# b294_rev0.net
KiCad netlist of a schematic drawn in EAGLE
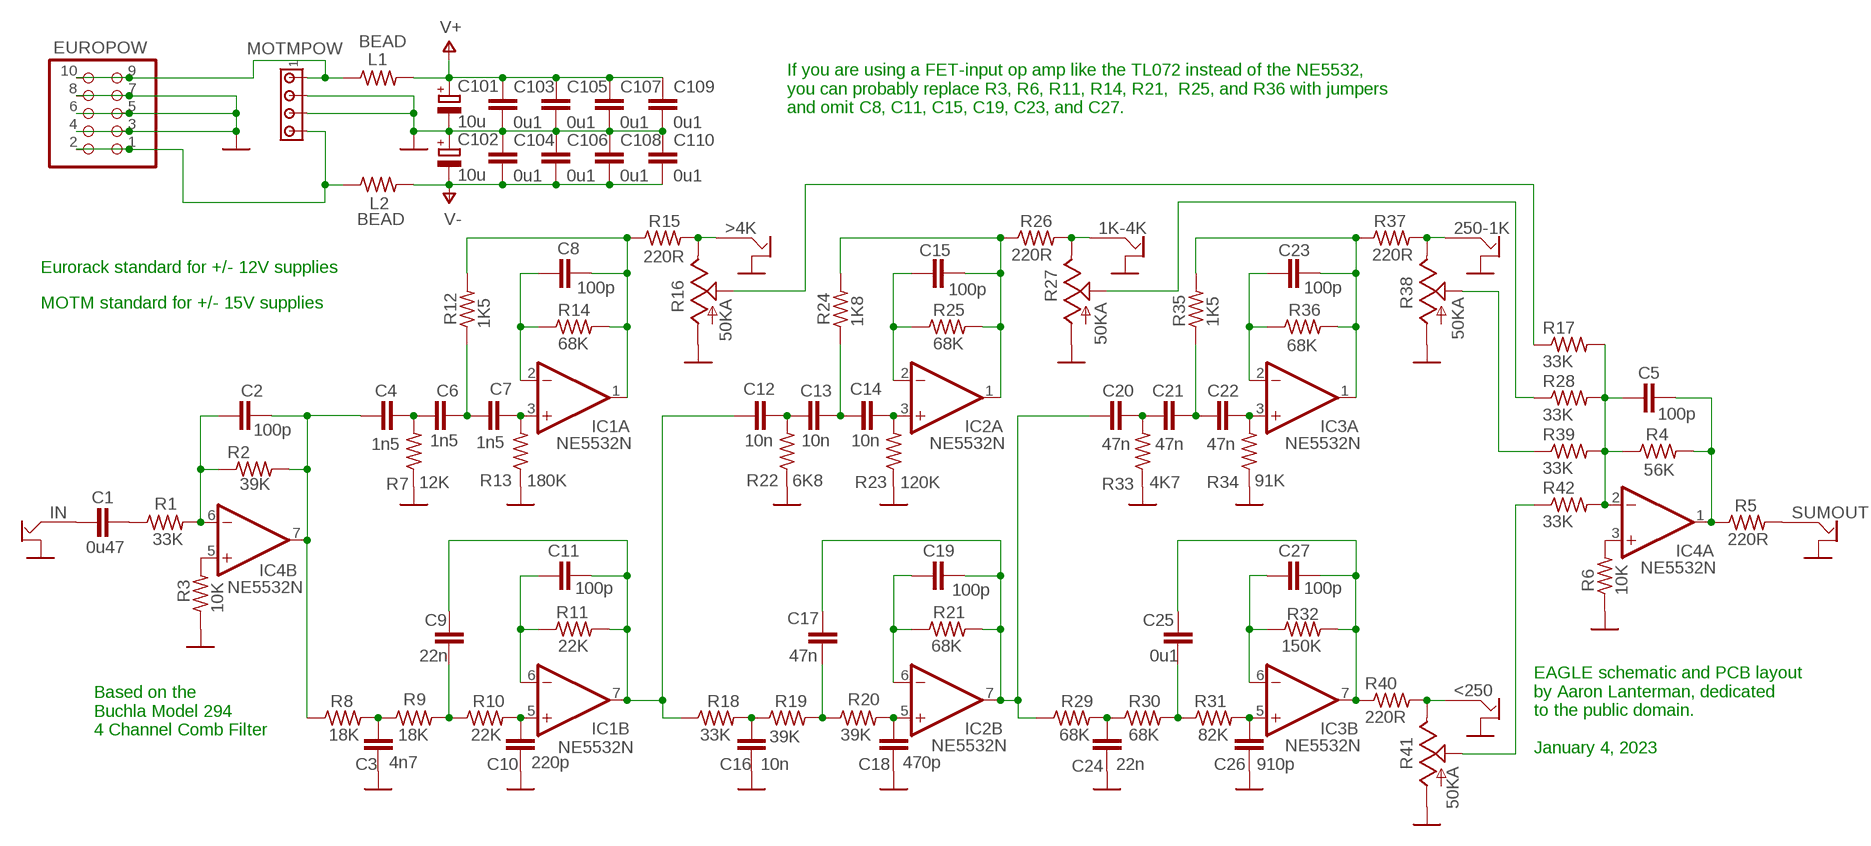
[diagram p0: schematic, sheet 1]

(export (version "E")
  (design (tool "Eeschema 10.0.6"))
  (components
    (comp (ref "1K-4K")
      (value "OFFBOARD2JACKALT_AARON")
      (footprint "eagle-import:OFFBOARD2JACKALT")
      (libsource (lib "eagle-import") (part "OFFBOARD2JACKALT_AARON"))
    )
    (comp (ref "250-1K")
      (value "OFFBOARD2JACKALT_AARON")
      (footprint "eagle-import:OFFBOARD2JACKALT")
      (libsource (lib "eagle-import") (part "OFFBOARD2JACKALT_AARON"))
    )
    (comp (ref "<250")
      (value "OFFBOARD2JACKALT_AARON")
      (footprint "eagle-import:OFFBOARD2JACKALT")
      (libsource (lib "eagle-import") (part "OFFBOARD2JACKALT_AARON"))
    )
    (comp (ref ">4K")
      (value "OFFBOARD2JACKALT_AARON")
      (footprint "eagle-import:OFFBOARD2JACKALT")
      (libsource (lib "eagle-import") (part "OFFBOARD2JACKALT_AARON"))
    )
    (comp (ref "C1")
      (value "0u47")
      (footprint "eagle-import:C050-025X075")
      (libsource (lib "eagle-import") (part "C-EU050-025X075"))
    )
    (comp (ref "C2")
      (value "100p")
      (footprint "eagle-import:C050-025X075")
      (libsource (lib "eagle-import") (part "C-EU050-025X075"))
    )
    (comp (ref "C3")
      (value "4n7")
      (footprint "eagle-import:C050-025X075")
      (libsource (lib "eagle-import") (part "C-EU050-025X075"))
    )
    (comp (ref "C4")
      (value "1n5")
      (footprint "eagle-import:C050-025X075")
      (libsource (lib "eagle-import") (part "C-EU050-025X075"))
    )
    (comp (ref "C5")
      (value "100p")
      (footprint "eagle-import:C050-025X075")
      (libsource (lib "eagle-import") (part "C-EU050-025X075"))
    )
    (comp (ref "C6")
      (value "1n5")
      (footprint "eagle-import:C050-025X075")
      (libsource (lib "eagle-import") (part "C-EU050-025X075"))
    )
    (comp (ref "C7")
      (value "1n5")
      (footprint "eagle-import:C050-025X075")
      (libsource (lib "eagle-import") (part "C-EU050-025X075"))
    )
    (comp (ref "C8")
      (value "100p")
      (footprint "eagle-import:C050-025X075")
      (libsource (lib "eagle-import") (part "C-EU050-025X075"))
    )
    (comp (ref "C9")
      (value "22n")
      (footprint "eagle-import:C050-025X075")
      (libsource (lib "eagle-import") (part "C-EU050-025X075"))
    )
    (comp (ref "C10")
      (value "220p")
      (footprint "eagle-import:C050-025X075")
      (libsource (lib "eagle-import") (part "C-EU050-025X075"))
    )
    (comp (ref "C11")
      (value "100p")
      (footprint "eagle-import:C050-025X075")
      (libsource (lib "eagle-import") (part "C-EU050-025X075"))
    )
    (comp (ref "C12")
      (value "10n")
      (footprint "eagle-import:C050-025X075")
      (libsource (lib "eagle-import") (part "C-EU050-025X075"))
    )
    (comp (ref "C13")
      (value "10n")
      (footprint "eagle-import:C050-025X075")
      (libsource (lib "eagle-import") (part "C-EU050-025X075"))
    )
    (comp (ref "C14")
      (value "10n")
      (footprint "eagle-import:C050-025X075")
      (libsource (lib "eagle-import") (part "C-EU050-025X075"))
    )
    (comp (ref "C15")
      (value "100p")
      (footprint "eagle-import:C050-025X075")
      (libsource (lib "eagle-import") (part "C-EU050-025X075"))
    )
    (comp (ref "C16")
      (value "10n")
      (footprint "eagle-import:C050-025X075")
      (libsource (lib "eagle-import") (part "C-EU050-025X075"))
    )
    (comp (ref "C17")
      (value "47n")
      (footprint "eagle-import:C050-025X075")
      (libsource (lib "eagle-import") (part "C-EU050-025X075"))
    )
    (comp (ref "C18")
      (value "470p")
      (footprint "eagle-import:C050-025X075")
      (libsource (lib "eagle-import") (part "C-EU050-025X075"))
    )
    (comp (ref "C19")
      (value "100p")
      (footprint "eagle-import:C050-025X075")
      (libsource (lib "eagle-import") (part "C-EU050-025X075"))
    )
    (comp (ref "C20")
      (value "47n")
      (footprint "eagle-import:C050-025X075")
      (libsource (lib "eagle-import") (part "C-EU050-025X075"))
    )
    (comp (ref "C21")
      (value "47n")
      (footprint "eagle-import:C050-025X075")
      (libsource (lib "eagle-import") (part "C-EU050-025X075"))
    )
    (comp (ref "C22")
      (value "47n")
      (footprint "eagle-import:C050-025X075")
      (libsource (lib "eagle-import") (part "C-EU050-025X075"))
    )
    (comp (ref "C23")
      (value "100p")
      (footprint "eagle-import:C050-025X075")
      (libsource (lib "eagle-import") (part "C-EU050-025X075"))
    )
    (comp (ref "C24")
      (value "22n")
      (footprint "eagle-import:C050-025X075")
      (libsource (lib "eagle-import") (part "C-EU050-025X075"))
    )
    (comp (ref "C25")
      (value "0u1")
      (footprint "eagle-import:C050-025X075")
      (libsource (lib "eagle-import") (part "C-EU050-025X075"))
    )
    (comp (ref "C26")
      (value "910p")
      (footprint "eagle-import:C050-025X075")
      (libsource (lib "eagle-import") (part "C-EU050-025X075"))
    )
    (comp (ref "C27")
      (value "100p")
      (footprint "eagle-import:C050-025X075")
      (libsource (lib "eagle-import") (part "C-EU050-025X075"))
    )
    (comp (ref "C101")
      (value "10u")
      (footprint "eagle-import:E1,8-4")
      (libsource (lib "eagle-import") (part "CPOL-EUE1.8-4"))
    )
    (comp (ref "C102")
      (value "10u")
      (footprint "eagle-import:E1,8-4")
      (libsource (lib "eagle-import") (part "CPOL-EUE1.8-4"))
    )
    (comp (ref "C103")
      (value "0u1")
      (footprint "eagle-import:C050-025X075")
      (libsource (lib "eagle-import") (part "C-EU050-025X075"))
    )
    (comp (ref "C104")
      (value "0u1")
      (footprint "eagle-import:C050-025X075")
      (libsource (lib "eagle-import") (part "C-EU050-025X075"))
    )
    (comp (ref "C105")
      (value "0u1")
      (footprint "eagle-import:C050-025X075")
      (libsource (lib "eagle-import") (part "C-EU050-025X075"))
    )
    (comp (ref "C106")
      (value "0u1")
      (footprint "eagle-import:C050-025X075")
      (libsource (lib "eagle-import") (part "C-EU050-025X075"))
    )
    (comp (ref "C107")
      (value "0u1")
      (footprint "eagle-import:C050-025X075")
      (libsource (lib "eagle-import") (part "C-EU050-025X075"))
    )
    (comp (ref "C108")
      (value "0u1")
      (footprint "eagle-import:C050-025X075")
      (libsource (lib "eagle-import") (part "C-EU050-025X075"))
    )
    (comp (ref "C109")
      (value "0u1")
      (footprint "eagle-import:C050-025X075")
      (libsource (lib "eagle-import") (part "C-EU050-025X075"))
    )
    (comp (ref "C110")
      (value "0u1")
      (footprint "eagle-import:C050-025X075")
      (libsource (lib "eagle-import") (part "C-EU050-025X075"))
    )
    (comp (ref "EUROPOW")
      (value "PINHD-2X5")
      (footprint "eagle-import:2X05")
      (libsource (lib "eagle-import") (part "PINHD-2X5"))
    )
    (comp (ref "IC1")
      (value "NE5532N")
      (footprint "eagle-import:DIL08")
      (libsource (lib "eagle-import") (part "NE5532N"))
    )
    (comp (ref "IC2")
      (value "NE5532N")
      (footprint "eagle-import:DIL08")
      (libsource (lib "eagle-import") (part "NE5532N"))
    )
    (comp (ref "IC3")
      (value "NE5532N")
      (footprint "eagle-import:DIL08")
      (libsource (lib "eagle-import") (part "NE5532N"))
    )
    (comp (ref "IC4")
      (value "NE5532N")
      (footprint "eagle-import:DIL08")
      (libsource (lib "eagle-import") (part "NE5532N"))
    )
    (comp (ref "IN")
      (value "OFFBOARD2JACKALT_AARON")
      (footprint "eagle-import:OFFBOARD2JACKALT")
      (libsource (lib "eagle-import") (part "OFFBOARD2JACKALT_AARON"))
    )
    (comp (ref "L1")
      (value "BEAD")
      (footprint "eagle-import:0207_10")
      (libsource (lib "eagle-import") (part "R-US_0207/10"))
    )
    (comp (ref "L2")
      (value "BEAD")
      (footprint "eagle-import:0207_10")
      (libsource (lib "eagle-import") (part "R-US_0207/10"))
    )
    (comp (ref "MOTMPOW")
      (value "MTA04-156")
      (footprint "eagle-import:1X4MTA")
      (libsource (lib "eagle-import") (part "MTA04-156"))
    )
    (comp (ref "R1")
      (value "33K")
      (footprint "eagle-import:0207_10")
      (libsource (lib "eagle-import") (part "R-US_0207/10"))
    )
    (comp (ref "R2")
      (value "39K")
      (footprint "eagle-import:0207_10")
      (libsource (lib "eagle-import") (part "R-US_0207/10"))
    )
    (comp (ref "R3")
      (value "10K")
      (footprint "eagle-import:0207_10")
      (libsource (lib "eagle-import") (part "R-US_0207/10"))
    )
    (comp (ref "R4")
      (value "56K")
      (footprint "eagle-import:0207_10")
      (libsource (lib "eagle-import") (part "R-US_0207/10"))
    )
    (comp (ref "R5")
      (value "220R")
      (footprint "eagle-import:0207_10")
      (libsource (lib "eagle-import") (part "R-US_0207/10"))
    )
    (comp (ref "R6")
      (value "10K")
      (footprint "eagle-import:0207_10")
      (libsource (lib "eagle-import") (part "R-US_0207/10"))
    )
    (comp (ref "R7")
      (value "12K")
      (footprint "eagle-import:0207_10")
      (libsource (lib "eagle-import") (part "R-US_0207/10"))
    )
    (comp (ref "R8")
      (value "18K")
      (footprint "eagle-import:0207_10")
      (libsource (lib "eagle-import") (part "R-US_0207/10"))
    )
    (comp (ref "R9")
      (value "18K")
      (footprint "eagle-import:0207_10")
      (libsource (lib "eagle-import") (part "R-US_0207/10"))
    )
    (comp (ref "R10")
      (value "22K")
      (footprint "eagle-import:0207_10")
      (libsource (lib "eagle-import") (part "R-US_0207/10"))
    )
    (comp (ref "R11")
      (value "22K")
      (footprint "eagle-import:0207_10")
      (libsource (lib "eagle-import") (part "R-US_0207/10"))
    )
    (comp (ref "R12")
      (value "1K5")
      (footprint "eagle-import:0207_10")
      (libsource (lib "eagle-import") (part "R-US_0207/10"))
    )
    (comp (ref "R13")
      (value "180K")
      (footprint "eagle-import:0207_10")
      (libsource (lib "eagle-import") (part "R-US_0207/10"))
    )
    (comp (ref "R14")
      (value "68K")
      (footprint "eagle-import:0207_10")
      (libsource (lib "eagle-import") (part "R-US_0207/10"))
    )
    (comp (ref "R15")
      (value "220R")
      (footprint "eagle-import:0207_10")
      (libsource (lib "eagle-import") (part "R-US_0207/10"))
    )
    (comp (ref "R16")
      (value "50KA")
      (footprint "eagle-import:B64Y")
      (libsource (lib "eagle-import") (part "TRIM_US-B64Y"))
    )
    (comp (ref "R17")
      (value "33K")
      (footprint "eagle-import:0207_10")
      (libsource (lib "eagle-import") (part "R-US_0207/10"))
    )
    (comp (ref "R18")
      (value "33K")
      (footprint "eagle-import:0207_10")
      (libsource (lib "eagle-import") (part "R-US_0207/10"))
    )
    (comp (ref "R19")
      (value "39K")
      (footprint "eagle-import:0207_10")
      (libsource (lib "eagle-import") (part "R-US_0207/10"))
    )
    (comp (ref "R20")
      (value "39K")
      (footprint "eagle-import:0207_10")
      (libsource (lib "eagle-import") (part "R-US_0207/10"))
    )
    (comp (ref "R21")
      (value "68K")
      (footprint "eagle-import:0207_10")
      (libsource (lib "eagle-import") (part "R-US_0207/10"))
    )
    (comp (ref "R22")
      (value "6K8")
      (footprint "eagle-import:0207_10")
      (libsource (lib "eagle-import") (part "R-US_0207/10"))
    )
    (comp (ref "R23")
      (value "120K")
      (footprint "eagle-import:0207_10")
      (libsource (lib "eagle-import") (part "R-US_0207/10"))
    )
    (comp (ref "R24")
      (value "1K8")
      (footprint "eagle-import:0207_10")
      (libsource (lib "eagle-import") (part "R-US_0207/10"))
    )
    (comp (ref "R25")
      (value "68K")
      (footprint "eagle-import:0207_10")
      (libsource (lib "eagle-import") (part "R-US_0207/10"))
    )
    (comp (ref "R26")
      (value "220R")
      (footprint "eagle-import:0207_10")
      (libsource (lib "eagle-import") (part "R-US_0207/10"))
    )
    (comp (ref "R27")
      (value "50KA")
      (footprint "eagle-import:B64Y")
      (libsource (lib "eagle-import") (part "TRIM_US-B64Y"))
    )
    (comp (ref "R28")
      (value "33K")
      (footprint "eagle-import:0207_10")
      (libsource (lib "eagle-import") (part "R-US_0207/10"))
    )
    (comp (ref "R29")
      (value "68K")
      (footprint "eagle-import:0207_10")
      (libsource (lib "eagle-import") (part "R-US_0207/10"))
    )
    (comp (ref "R30")
      (value "68K")
      (footprint "eagle-import:0207_10")
      (libsource (lib "eagle-import") (part "R-US_0207/10"))
    )
    (comp (ref "R31")
      (value "82K")
      (footprint "eagle-import:0207_10")
      (libsource (lib "eagle-import") (part "R-US_0207/10"))
    )
    (comp (ref "R32")
      (value "150K")
      (footprint "eagle-import:0207_10")
      (libsource (lib "eagle-import") (part "R-US_0207/10"))
    )
    (comp (ref "R33")
      (value "4K7")
      (footprint "eagle-import:0207_10")
      (libsource (lib "eagle-import") (part "R-US_0207/10"))
    )
    (comp (ref "R34")
      (value "91K")
      (footprint "eagle-import:0207_10")
      (libsource (lib "eagle-import") (part "R-US_0207/10"))
    )
    (comp (ref "R35")
      (value "1K5")
      (footprint "eagle-import:0207_10")
      (libsource (lib "eagle-import") (part "R-US_0207/10"))
    )
    (comp (ref "R36")
      (value "68K")
      (footprint "eagle-import:0207_10")
      (libsource (lib "eagle-import") (part "R-US_0207/10"))
    )
    (comp (ref "R37")
      (value "220R")
      (footprint "eagle-import:0207_10")
      (libsource (lib "eagle-import") (part "R-US_0207/10"))
    )
    (comp (ref "R38")
      (value "50KA")
      (footprint "eagle-import:B64Y")
      (libsource (lib "eagle-import") (part "TRIM_US-B64Y"))
    )
    (comp (ref "R39")
      (value "33K")
      (footprint "eagle-import:0207_10")
      (libsource (lib "eagle-import") (part "R-US_0207/10"))
    )
    (comp (ref "R40")
      (value "220R")
      (footprint "eagle-import:0207_10")
      (libsource (lib "eagle-import") (part "R-US_0207/10"))
    )
    (comp (ref "R41")
      (value "50KA")
      (footprint "eagle-import:B64Y")
      (libsource (lib "eagle-import") (part "TRIM_US-B64Y"))
    )
    (comp (ref "R42")
      (value "33K")
      (footprint "eagle-import:0207_10")
      (libsource (lib "eagle-import") (part "R-US_0207/10"))
    )
    (comp (ref "SUMOUT")
      (value "OFFBOARD2JACKALT_AARON")
      (footprint "eagle-import:OFFBOARD2JACKALT")
      (libsource (lib "eagle-import") (part "OFFBOARD2JACKALT_AARON"))
    )
  )
  (nets
    (net (code "1") (name "GND") (class "Default")
      (node (ref "1K-4K") (pin "GND") (pinfunction "GND_GND") (pintype "passive"))
      (node (ref "250-1K") (pin "GND") (pinfunction "GND_GND") (pintype "passive"))
      (node (ref "<250") (pin "GND") (pinfunction "GND_GND") (pintype "passive"))
      (node (ref ">4K") (pin "GND") (pinfunction "GND_GND") (pintype "passive"))
      (node (ref "C10") (pin "2") (pinfunction "2_2") (pintype "passive"))
      (node (ref "C101") (pin "-") (pinfunction "-_-") (pintype "passive"))
      (node (ref "C102") (pin "+") (pinfunction "+_+") (pintype "passive"))
      (node (ref "C103") (pin "2") (pinfunction "2_2") (pintype "passive"))
      (node (ref "C104") (pin "1") (pinfunction "1_1") (pintype "passive"))
      (node (ref "C105") (pin "2") (pinfunction "2_2") (pintype "passive"))
      (node (ref "C106") (pin "1") (pinfunction "1_1") (pintype "passive"))
      (node (ref "C107") (pin "2") (pinfunction "2_2") (pintype "passive"))
      (node (ref "C108") (pin "1") (pinfunction "1_1") (pintype "passive"))
      (node (ref "C109") (pin "2") (pinfunction "2_2") (pintype "passive"))
      (node (ref "C110") (pin "1") (pinfunction "1_1") (pintype "passive"))
      (node (ref "C16") (pin "2") (pinfunction "2_2") (pintype "passive"))
      (node (ref "C18") (pin "2") (pinfunction "2_2") (pintype "passive"))
      (node (ref "C24") (pin "2") (pinfunction "2_2") (pintype "passive"))
      (node (ref "C26") (pin "2") (pinfunction "2_2") (pintype "passive"))
      (node (ref "C3") (pin "2") (pinfunction "2_2") (pintype "passive"))
      (node (ref "EUROPOW") (pin "3") (pinfunction "3_3") (pintype "passive"))
      (node (ref "EUROPOW") (pin "4") (pinfunction "4_4") (pintype "passive"))
      (node (ref "EUROPOW") (pin "5") (pinfunction "5_5") (pintype "passive"))
      (node (ref "EUROPOW") (pin "6") (pinfunction "6_6") (pintype "passive"))
      (node (ref "EUROPOW") (pin "7") (pinfunction "7_7") (pintype "passive"))
      (node (ref "EUROPOW") (pin "8") (pinfunction "8_8") (pintype "passive"))
      (node (ref "IN") (pin "GND") (pinfunction "GND_GND") (pintype "passive"))
      (node (ref "MOTMPOW") (pin "2") (pinfunction "2_2") (pintype "passive"))
      (node (ref "MOTMPOW") (pin "3") (pinfunction "3_3") (pintype "passive"))
      (node (ref "R13") (pin "1") (pinfunction "1_1") (pintype "passive"))
      (node (ref "R16") (pin "A") (pinfunction "A_A") (pintype "passive"))
      (node (ref "R22") (pin "1") (pinfunction "1_1") (pintype "passive"))
      (node (ref "R23") (pin "1") (pinfunction "1_1") (pintype "passive"))
      (node (ref "R27") (pin "A") (pinfunction "A_A") (pintype "passive"))
      (node (ref "R3") (pin "1") (pinfunction "1_1") (pintype "passive"))
      (node (ref "R33") (pin "1") (pinfunction "1_1") (pintype "passive"))
      (node (ref "R34") (pin "1") (pinfunction "1_1") (pintype "passive"))
      (node (ref "R38") (pin "A") (pinfunction "A_A") (pintype "passive"))
      (node (ref "R41") (pin "A") (pinfunction "A_A") (pintype "passive"))
      (node (ref "R6") (pin "1") (pinfunction "1_1") (pintype "passive"))
      (node (ref "R7") (pin "1") (pinfunction "1_1") (pintype "passive"))
      (node (ref "SUMOUT") (pin "GND") (pinfunction "GND_GND") (pintype "passive"))
    )
    (net (code "2") (name "Net-(1K-4K-PadSIGNAL)") (class "Default")
      (node (ref "1K-4K") (pin "SIGNAL") (pinfunction "SIGNAL_SIGNAL") (pintype "passive"))
      (node (ref "R26") (pin "2") (pinfunction "2_2") (pintype "passive"))
      (node (ref "R27") (pin "E") (pinfunction "E_E") (pintype "passive"))
    )
    (net (code "3") (name "Net-(250-1K-PadSIGNAL)") (class "Default")
      (node (ref "250-1K") (pin "SIGNAL") (pinfunction "SIGNAL_SIGNAL") (pintype "passive"))
      (node (ref "R37") (pin "2") (pinfunction "2_2") (pintype "passive"))
      (node (ref "R38") (pin "E") (pinfunction "E_E") (pintype "passive"))
    )
    (net (code "4") (name "Net-(<250-PadSIGNAL)") (class "Default")
      (node (ref "<250") (pin "SIGNAL") (pinfunction "SIGNAL_SIGNAL") (pintype "passive"))
      (node (ref "R40") (pin "2") (pinfunction "2_2") (pintype "passive"))
      (node (ref "R41") (pin "E") (pinfunction "E_E") (pintype "passive"))
    )
    (net (code "5") (name "Net-(>4K-PadSIGNAL)") (class "Default")
      (node (ref ">4K") (pin "SIGNAL") (pinfunction "SIGNAL_SIGNAL") (pintype "passive"))
      (node (ref "R15") (pin "2") (pinfunction "2_2") (pintype "passive"))
      (node (ref "R16") (pin "E") (pinfunction "E_E") (pintype "passive"))
    )
    (net (code "6") (name "Net-(C1-Pad1)") (class "Default")
      (node (ref "C1") (pin "1") (pinfunction "1_1") (pintype "passive"))
      (node (ref "IN") (pin "SIGNAL") (pinfunction "SIGNAL_SIGNAL") (pintype "passive"))
    )
    (net (code "7") (name "Net-(C1-Pad2)") (class "Default")
      (node (ref "C1") (pin "2") (pinfunction "2_2") (pintype "passive"))
      (node (ref "R1") (pin "1") (pinfunction "1_1") (pintype "passive"))
    )
    (net (code "8") (name "Net-(C3-Pad1)") (class "Default")
      (node (ref "C3") (pin "1") (pinfunction "1_1") (pintype "passive"))
      (node (ref "R8") (pin "2") (pinfunction "2_2") (pintype "passive"))
      (node (ref "R9") (pin "1") (pinfunction "1_1") (pintype "passive"))
    )
    (net (code "9") (name "Net-(C4-Pad2)") (class "Default")
      (node (ref "C4") (pin "2") (pinfunction "2_2") (pintype "passive"))
      (node (ref "C6") (pin "1") (pinfunction "1_1") (pintype "passive"))
      (node (ref "R7") (pin "2") (pinfunction "2_2") (pintype "passive"))
    )
    (net (code "10") (name "Net-(C6-Pad2)") (class "Default")
      (node (ref "C6") (pin "2") (pinfunction "2_2") (pintype "passive"))
      (node (ref "C7") (pin "1") (pinfunction "1_1") (pintype "passive"))
      (node (ref "R12") (pin "1") (pinfunction "1_1") (pintype "passive"))
    )
    (net (code "11") (name "Net-(C9-Pad2)") (class "Default")
      (node (ref "C9") (pin "2") (pinfunction "2_2") (pintype "passive"))
      (node (ref "R10") (pin "1") (pinfunction "1_1") (pintype "passive"))
      (node (ref "R9") (pin "2") (pinfunction "2_2") (pintype "passive"))
    )
    (net (code "12") (name "Net-(C12-Pad2)") (class "Default")
      (node (ref "C12") (pin "2") (pinfunction "2_2") (pintype "passive"))
      (node (ref "C13") (pin "1") (pinfunction "1_1") (pintype "passive"))
      (node (ref "R22") (pin "2") (pinfunction "2_2") (pintype "passive"))
    )
    (net (code "13") (name "Net-(C13-Pad2)") (class "Default")
      (node (ref "C13") (pin "2") (pinfunction "2_2") (pintype "passive"))
      (node (ref "C14") (pin "1") (pinfunction "1_1") (pintype "passive"))
      (node (ref "R24") (pin "1") (pinfunction "1_1") (pintype "passive"))
    )
    (net (code "14") (name "Net-(C16-Pad1)") (class "Default")
      (node (ref "C16") (pin "1") (pinfunction "1_1") (pintype "passive"))
      (node (ref "R18") (pin "2") (pinfunction "2_2") (pintype "passive"))
      (node (ref "R19") (pin "1") (pinfunction "1_1") (pintype "passive"))
    )
    (net (code "15") (name "Net-(C17-Pad2)") (class "Default")
      (node (ref "C17") (pin "2") (pinfunction "2_2") (pintype "passive"))
      (node (ref "R19") (pin "2") (pinfunction "2_2") (pintype "passive"))
      (node (ref "R20") (pin "1") (pinfunction "1_1") (pintype "passive"))
    )
    (net (code "16") (name "Net-(C20-Pad2)") (class "Default")
      (node (ref "C20") (pin "2") (pinfunction "2_2") (pintype "passive"))
      (node (ref "C21") (pin "1") (pinfunction "1_1") (pintype "passive"))
      (node (ref "R33") (pin "2") (pinfunction "2_2") (pintype "passive"))
    )
    (net (code "17") (name "Net-(C21-Pad2)") (class "Default")
      (node (ref "C21") (pin "2") (pinfunction "2_2") (pintype "passive"))
      (node (ref "C22") (pin "1") (pinfunction "1_1") (pintype "passive"))
      (node (ref "R35") (pin "1") (pinfunction "1_1") (pintype "passive"))
    )
    (net (code "18") (name "Net-(C24-Pad1)") (class "Default")
      (node (ref "C24") (pin "1") (pinfunction "1_1") (pintype "passive"))
      (node (ref "R29") (pin "2") (pinfunction "2_2") (pintype "passive"))
      (node (ref "R30") (pin "1") (pinfunction "1_1") (pintype "passive"))
    )
    (net (code "19") (name "Net-(C25-Pad2)") (class "Default")
      (node (ref "C25") (pin "2") (pinfunction "2_2") (pintype "passive"))
      (node (ref "R30") (pin "2") (pinfunction "2_2") (pintype "passive"))
      (node (ref "R31") (pin "1") (pinfunction "1_1") (pintype "passive"))
    )
    (net (code "20") (name "Net-(EUROPOW-Pad1)") (class "Default")
      (node (ref "EUROPOW") (pin "1") (pinfunction "1_1") (pintype "passive"))
      (node (ref "EUROPOW") (pin "2") (pinfunction "2_2") (pintype "passive"))
      (node (ref "L2") (pin "1") (pinfunction "1_1") (pintype "passive"))
      (node (ref "MOTMPOW") (pin "4") (pinfunction "4_4") (pintype "passive"))
    )
    (net (code "21") (name "Net-(EUROPOW-Pad10)") (class "Default")
      (node (ref "EUROPOW") (pin "10") (pinfunction "10_10") (pintype "passive"))
      (node (ref "EUROPOW") (pin "9") (pinfunction "9_9") (pintype "passive"))
      (node (ref "L1") (pin "1") (pinfunction "1_1") (pintype "passive"))
      (node (ref "MOTMPOW") (pin "1") (pinfunction "1_1") (pintype "passive"))
    )
    (net (code "22") (name "Net-(IC1A-+IN)") (class "Default")
      (node (ref "C7") (pin "2") (pinfunction "2_2") (pintype "passive"))
      (node (ref "IC1") (pin "3") (pinfunction "+IN_3") (pintype "input"))
      (node (ref "R13") (pin "2") (pinfunction "2_2") (pintype "passive"))
    )
    (net (code "23") (name "Net-(IC1A--IN)") (class "Default")
      (node (ref "C8") (pin "1") (pinfunction "1_1") (pintype "passive"))
      (node (ref "IC1") (pin "2") (pinfunction "-IN_2") (pintype "input"))
      (node (ref "R14") (pin "1") (pinfunction "1_1") (pintype "passive"))
    )
    (net (code "24") (name "Net-(IC1A-OUT)") (class "Default")
      (node (ref "C8") (pin "2") (pinfunction "2_2") (pintype "passive"))
      (node (ref "IC1") (pin "1") (pinfunction "OUT_1") (pintype "output"))
      (node (ref "R12") (pin "2") (pinfunction "2_2") (pintype "passive"))
      (node (ref "R14") (pin "2") (pinfunction "2_2") (pintype "passive"))
      (node (ref "R15") (pin "1") (pinfunction "1_1") (pintype "passive"))
    )
    (net (code "25") (name "Net-(IC1B-+IN)") (class "Default")
      (node (ref "C10") (pin "1") (pinfunction "1_1") (pintype "passive"))
      (node (ref "IC1") (pin "5") (pinfunction "+IN_5") (pintype "input"))
      (node (ref "R10") (pin "2") (pinfunction "2_2") (pintype "passive"))
    )
    (net (code "26") (name "Net-(IC1B--IN)") (class "Default")
      (node (ref "C11") (pin "1") (pinfunction "1_1") (pintype "passive"))
      (node (ref "IC1") (pin "6") (pinfunction "-IN_6") (pintype "input"))
      (node (ref "R11") (pin "1") (pinfunction "1_1") (pintype "passive"))
    )
    (net (code "27") (name "Net-(IC1B-OUT)") (class "Default")
      (node (ref "C11") (pin "2") (pinfunction "2_2") (pintype "passive"))
      (node (ref "C12") (pin "1") (pinfunction "1_1") (pintype "passive"))
      (node (ref "C9") (pin "1") (pinfunction "1_1") (pintype "passive"))
      (node (ref "IC1") (pin "7") (pinfunction "OUT_7") (pintype "output"))
      (node (ref "R11") (pin "2") (pinfunction "2_2") (pintype "passive"))
      (node (ref "R18") (pin "1") (pinfunction "1_1") (pintype "passive"))
    )
    (net (code "28") (name "Net-(IC2A-+IN)") (class "Default")
      (node (ref "C14") (pin "2") (pinfunction "2_2") (pintype "passive"))
      (node (ref "IC2") (pin "3") (pinfunction "+IN_3") (pintype "input"))
      (node (ref "R23") (pin "2") (pinfunction "2_2") (pintype "passive"))
    )
    (net (code "29") (name "Net-(IC2A--IN)") (class "Default")
      (node (ref "C15") (pin "1") (pinfunction "1_1") (pintype "passive"))
      (node (ref "IC2") (pin "2") (pinfunction "-IN_2") (pintype "input"))
      (node (ref "R25") (pin "1") (pinfunction "1_1") (pintype "passive"))
    )
    (net (code "30") (name "Net-(IC2A-OUT)") (class "Default")
      (node (ref "C15") (pin "2") (pinfunction "2_2") (pintype "passive"))
      (node (ref "IC2") (pin "1") (pinfunction "OUT_1") (pintype "output"))
      (node (ref "R24") (pin "2") (pinfunction "2_2") (pintype "passive"))
      (node (ref "R25") (pin "2") (pinfunction "2_2") (pintype "passive"))
      (node (ref "R26") (pin "1") (pinfunction "1_1") (pintype "passive"))
    )
    (net (code "31") (name "Net-(IC2B-+IN)") (class "Default")
      (node (ref "C18") (pin "1") (pinfunction "1_1") (pintype "passive"))
      (node (ref "IC2") (pin "5") (pinfunction "+IN_5") (pintype "input"))
      (node (ref "R20") (pin "2") (pinfunction "2_2") (pintype "passive"))
    )
    (net (code "32") (name "Net-(IC2B--IN)") (class "Default")
      (node (ref "C19") (pin "1") (pinfunction "1_1") (pintype "passive"))
      (node (ref "IC2") (pin "6") (pinfunction "-IN_6") (pintype "input"))
      (node (ref "R21") (pin "1") (pinfunction "1_1") (pintype "passive"))
    )
    (net (code "33") (name "Net-(IC2B-OUT)") (class "Default")
      (node (ref "C17") (pin "1") (pinfunction "1_1") (pintype "passive"))
      (node (ref "C19") (pin "2") (pinfunction "2_2") (pintype "passive"))
      (node (ref "C20") (pin "1") (pinfunction "1_1") (pintype "passive"))
      (node (ref "IC2") (pin "7") (pinfunction "OUT_7") (pintype "output"))
      (node (ref "R21") (pin "2") (pinfunction "2_2") (pintype "passive"))
      (node (ref "R29") (pin "1") (pinfunction "1_1") (pintype "passive"))
    )
    (net (code "34") (name "Net-(IC3A-+IN)") (class "Default")
      (node (ref "C22") (pin "2") (pinfunction "2_2") (pintype "passive"))
      (node (ref "IC3") (pin "3") (pinfunction "+IN_3") (pintype "input"))
      (node (ref "R34") (pin "2") (pinfunction "2_2") (pintype "passive"))
    )
    (net (code "35") (name "Net-(IC3A--IN)") (class "Default")
      (node (ref "C23") (pin "1") (pinfunction "1_1") (pintype "passive"))
      (node (ref "IC3") (pin "2") (pinfunction "-IN_2") (pintype "input"))
      (node (ref "R36") (pin "1") (pinfunction "1_1") (pintype "passive"))
    )
    (net (code "36") (name "Net-(IC3A-OUT)") (class "Default")
      (node (ref "C23") (pin "2") (pinfunction "2_2") (pintype "passive"))
      (node (ref "IC3") (pin "1") (pinfunction "OUT_1") (pintype "output"))
      (node (ref "R35") (pin "2") (pinfunction "2_2") (pintype "passive"))
      (node (ref "R36") (pin "2") (pinfunction "2_2") (pintype "passive"))
      (node (ref "R37") (pin "1") (pinfunction "1_1") (pintype "passive"))
    )
    (net (code "37") (name "Net-(IC3B-+IN)") (class "Default")
      (node (ref "C26") (pin "1") (pinfunction "1_1") (pintype "passive"))
      (node (ref "IC3") (pin "5") (pinfunction "+IN_5") (pintype "input"))
      (node (ref "R31") (pin "2") (pinfunction "2_2") (pintype "passive"))
    )
    (net (code "38") (name "Net-(IC3B--IN)") (class "Default")
      (node (ref "C27") (pin "1") (pinfunction "1_1") (pintype "passive"))
      (node (ref "IC3") (pin "6") (pinfunction "-IN_6") (pintype "input"))
      (node (ref "R32") (pin "1") (pinfunction "1_1") (pintype "passive"))
    )
    (net (code "39") (name "Net-(IC3B-OUT)") (class "Default")
      (node (ref "C25") (pin "1") (pinfunction "1_1") (pintype "passive"))
      (node (ref "C27") (pin "2") (pinfunction "2_2") (pintype "passive"))
      (node (ref "IC3") (pin "7") (pinfunction "OUT_7") (pintype "output"))
      (node (ref "R32") (pin "2") (pinfunction "2_2") (pintype "passive"))
      (node (ref "R40") (pin "1") (pinfunction "1_1") (pintype "passive"))
    )
    (net (code "40") (name "Net-(IC4A-+IN)") (class "Default")
      (node (ref "IC4") (pin "3") (pinfunction "+IN_3") (pintype "input"))
      (node (ref "R6") (pin "2") (pinfunction "2_2") (pintype "passive"))
    )
    (net (code "41") (name "Net-(IC4A--IN)") (class "Default")
      (node (ref "C5") (pin "1") (pinfunction "1_1") (pintype "passive"))
      (node (ref "IC4") (pin "2") (pinfunction "-IN_2") (pintype "input"))
      (node (ref "R17") (pin "2") (pinfunction "2_2") (pintype "passive"))
      (node (ref "R28") (pin "2") (pinfunction "2_2") (pintype "passive"))
      (node (ref "R39") (pin "2") (pinfunction "2_2") (pintype "passive"))
      (node (ref "R4") (pin "1") (pinfunction "1_1") (pintype "passive"))
      (node (ref "R42") (pin "2") (pinfunction "2_2") (pintype "passive"))
    )
    (net (code "42") (name "Net-(IC4A-OUT)") (class "Default")
      (node (ref "C5") (pin "2") (pinfunction "2_2") (pintype "passive"))
      (node (ref "IC4") (pin "1") (pinfunction "OUT_1") (pintype "output"))
      (node (ref "R4") (pin "2") (pinfunction "2_2") (pintype "passive"))
      (node (ref "R5") (pin "1") (pinfunction "1_1") (pintype "passive"))
    )
    (net (code "43") (name "Net-(IC4B-+IN)") (class "Default")
      (node (ref "IC4") (pin "5") (pinfunction "+IN_5") (pintype "input"))
      (node (ref "R3") (pin "2") (pinfunction "2_2") (pintype "passive"))
    )
    (net (code "44") (name "Net-(IC4B--IN)") (class "Default")
      (node (ref "C2") (pin "1") (pinfunction "1_1") (pintype "passive"))
      (node (ref "IC4") (pin "6") (pinfunction "-IN_6") (pintype "input"))
      (node (ref "R1") (pin "2") (pinfunction "2_2") (pintype "passive"))
      (node (ref "R2") (pin "1") (pinfunction "1_1") (pintype "passive"))
    )
    (net (code "45") (name "Net-(IC4B-OUT)") (class "Default")
      (node (ref "C2") (pin "2") (pinfunction "2_2") (pintype "passive"))
      (node (ref "C4") (pin "1") (pinfunction "1_1") (pintype "passive"))
      (node (ref "IC4") (pin "7") (pinfunction "OUT_7") (pintype "output"))
      (node (ref "R2") (pin "2") (pinfunction "2_2") (pintype "passive"))
      (node (ref "R8") (pin "1") (pinfunction "1_1") (pintype "passive"))
    )
    (net (code "46") (name "Net-(R5-Pad2)") (class "Default")
      (node (ref "R5") (pin "2") (pinfunction "2_2") (pintype "passive"))
      (node (ref "SUMOUT") (pin "SIGNAL") (pinfunction "SIGNAL_SIGNAL") (pintype "passive"))
    )
    (net (code "47") (name "Net-(R16-PadS)") (class "Default")
      (node (ref "R16") (pin "S") (pinfunction "S_S") (pintype "passive"))
      (node (ref "R17") (pin "1") (pinfunction "1_1") (pintype "passive"))
    )
    (net (code "48") (name "Net-(R27-PadS)") (class "Default")
      (node (ref "R27") (pin "S") (pinfunction "S_S") (pintype "passive"))
      (node (ref "R28") (pin "1") (pinfunction "1_1") (pintype "passive"))
    )
    (net (code "49") (name "Net-(R38-PadS)") (class "Default")
      (node (ref "R38") (pin "S") (pinfunction "S_S") (pintype "passive"))
      (node (ref "R39") (pin "1") (pinfunction "1_1") (pintype "passive"))
    )
    (net (code "50") (name "Net-(R41-PadS)") (class "Default")
      (node (ref "R41") (pin "S") (pinfunction "S_S") (pintype "passive"))
      (node (ref "R42") (pin "1") (pinfunction "1_1") (pintype "passive"))
    )
    (net (code "51") (name "V+") (class "Default")
      (node (ref "C101") (pin "+") (pinfunction "+_+") (pintype "passive"))
      (node (ref "C103") (pin "1") (pinfunction "1_1") (pintype "passive"))
      (node (ref "C105") (pin "1") (pinfunction "1_1") (pintype "passive"))
      (node (ref "C107") (pin "1") (pinfunction "1_1") (pintype "passive"))
      (node (ref "C109") (pin "1") (pinfunction "1_1") (pintype "passive"))
      (node (ref "L1") (pin "2") (pinfunction "2_2") (pintype "passive"))
    )
    (net (code "52") (name "V-") (class "Default")
      (node (ref "C102") (pin "-") (pinfunction "-_-") (pintype "passive"))
      (node (ref "C104") (pin "2") (pinfunction "2_2") (pintype "passive"))
      (node (ref "C106") (pin "2") (pinfunction "2_2") (pintype "passive"))
      (node (ref "C108") (pin "2") (pinfunction "2_2") (pintype "passive"))
      (node (ref "C110") (pin "2") (pinfunction "2_2") (pintype "passive"))
      (node (ref "L2") (pin "2") (pinfunction "2_2") (pintype "passive"))
    )
  )
)
